# Bank_3.net
KiCad netlist of a schematic drawn in Altium Designer
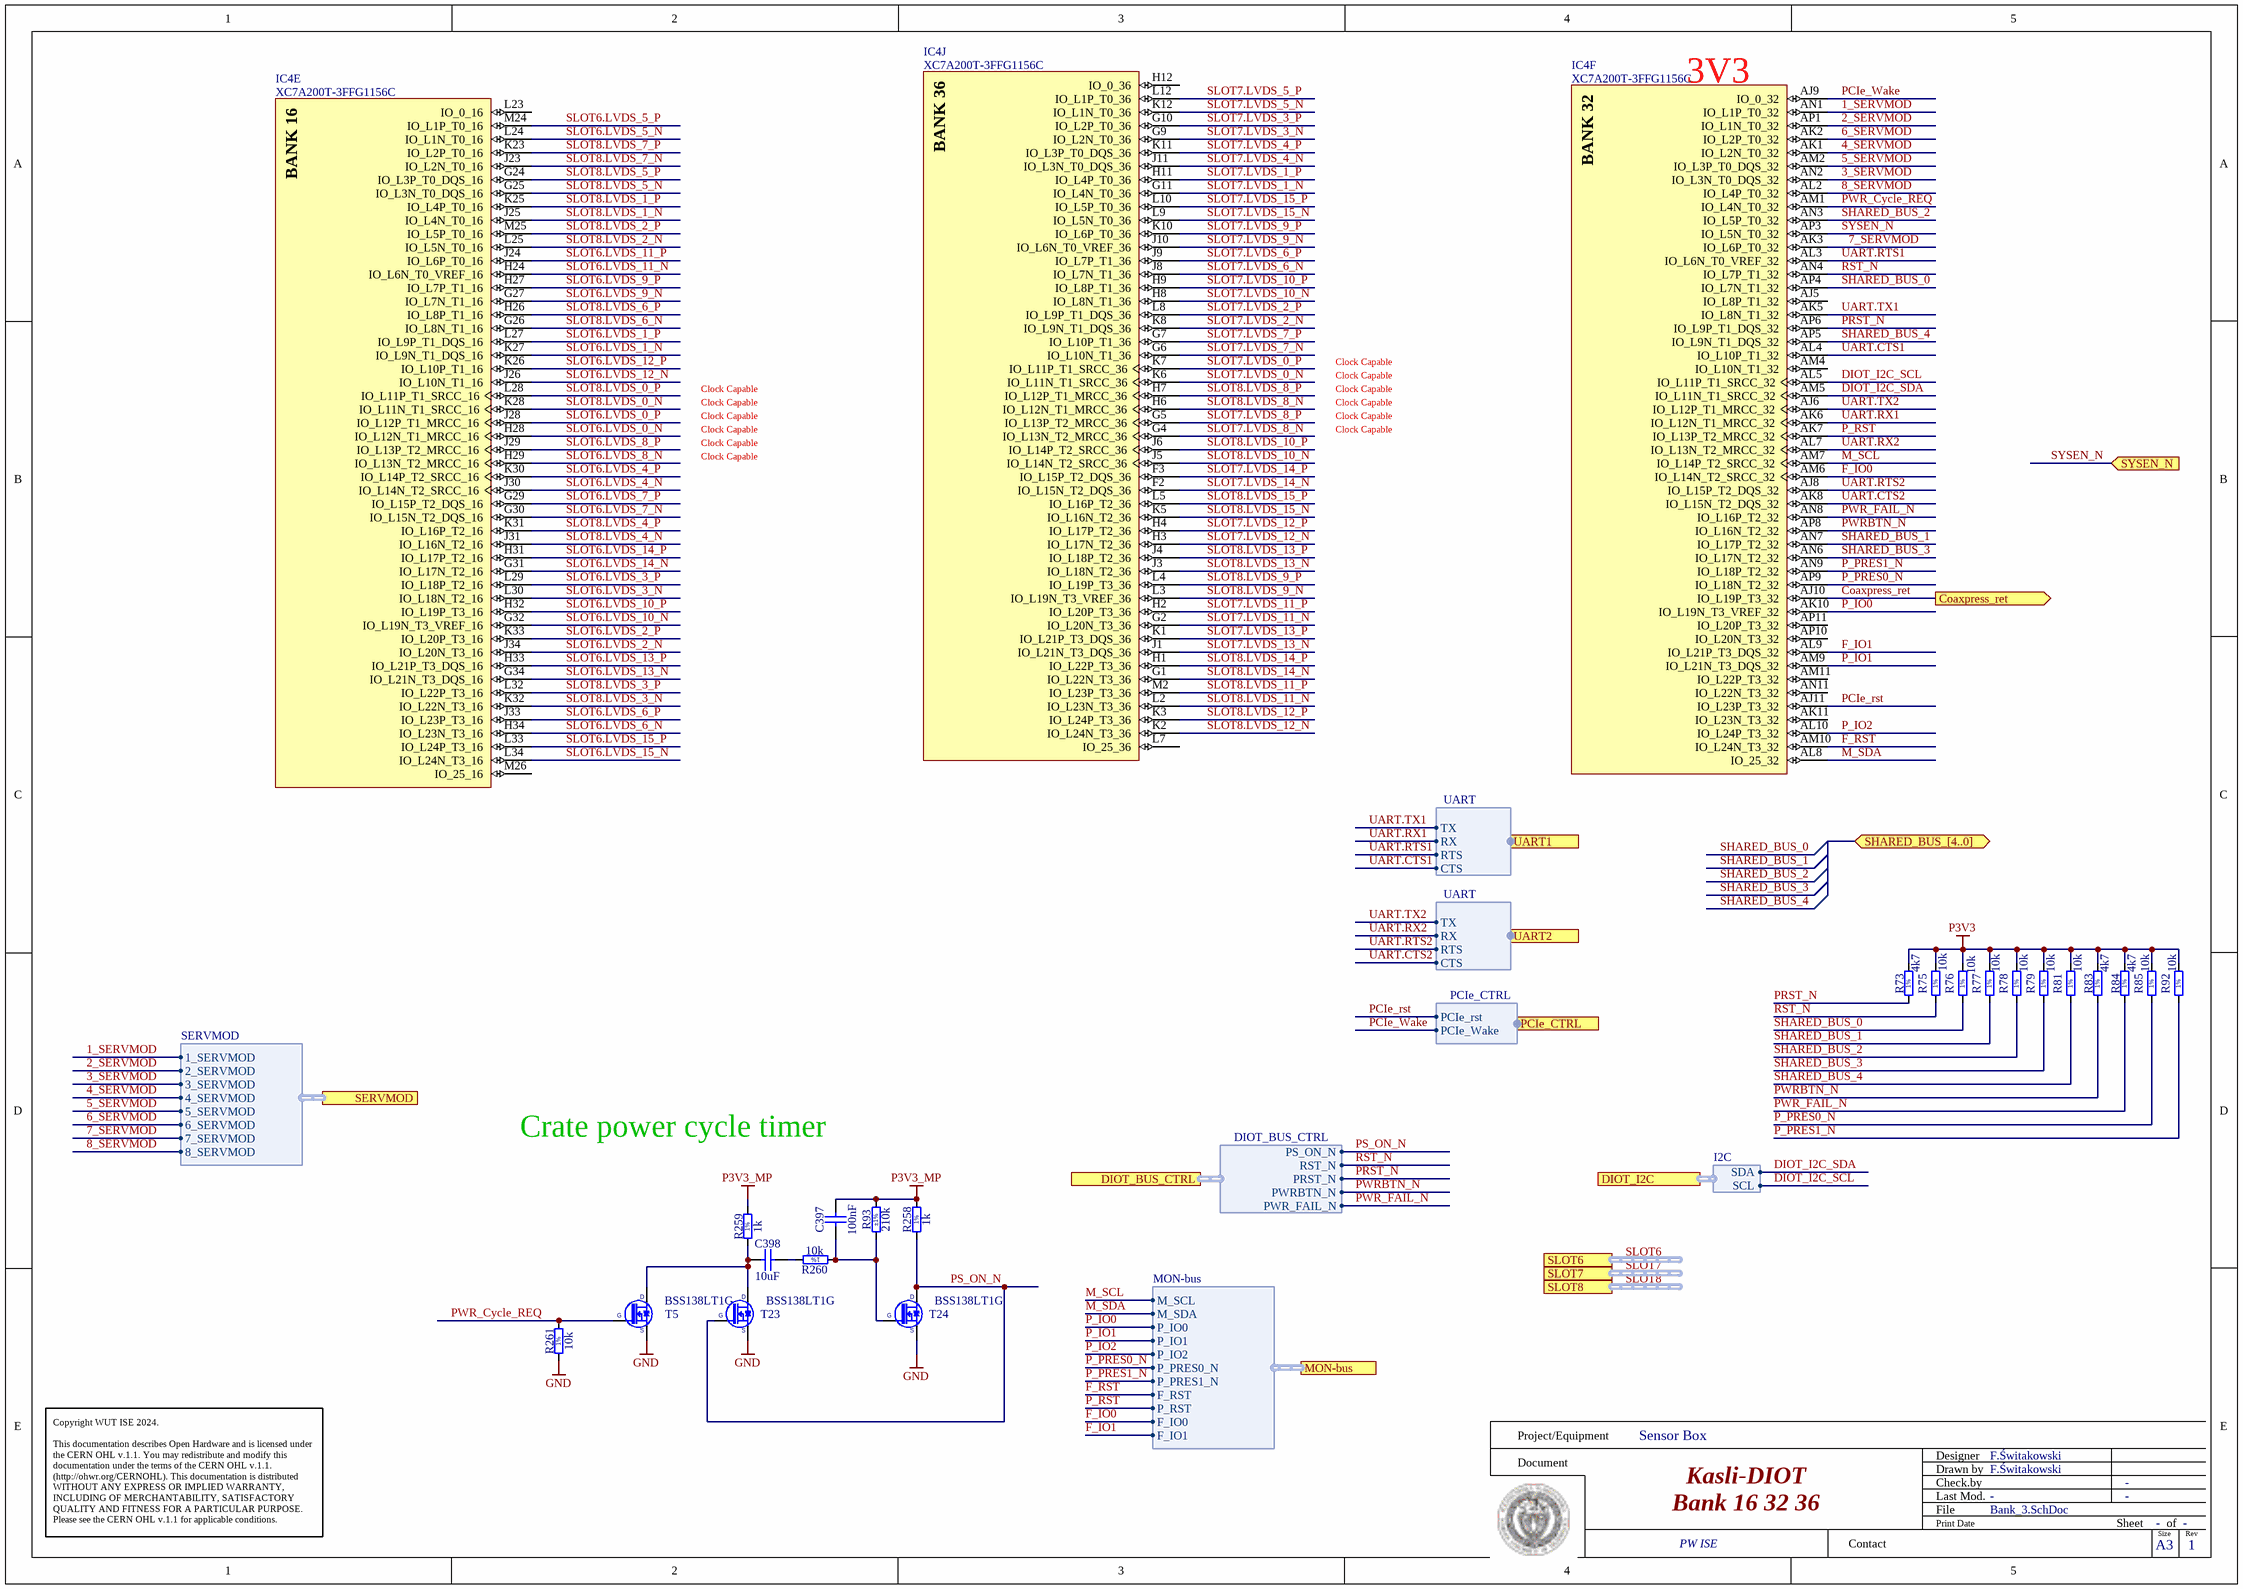
[diagram p0: Bank_3.SchDoc]

(export (version "E")
  (design (tool "Eeschema 10.0.6"))
  (components
    (comp (ref "C397")
      (value "100nF")
      (footprint "CAPC1005X55N")
      (description "Non-polarised capacitor")
      (fields
        (field (name "PART NUMBER") "CC0402_100NF_16V_10%_X7R")
        (field (name "VOLTAGE") "16V")
        (field (name "AUTHOR") "CERN DEM JLC")
      )
      (libsource (lib "Capacitors") (part "Capacitor - non polarized"))
    )
    (comp (ref "C398")
      (value "10uF")
      (footprint "CAPC3216X180N")
      (description "Non-polarised capacitor")
      (fields
        (field (name "PART NUMBER") "CC1206_10UF_25V_10%_X7R")
        (field (name "VOLTAGE") "25V")
        (field (name "AUTHOR") "CERN DEM JLC")
      )
      (libsource (lib "Capacitors") (part "Capacitor - non polarized"))
    )
    (comp (ref "IC4")
      (value "XC7A200T-3FFG1156C")
      (footprint "BGA1156C100P34X34_3500X3500X310")
      (description "Artix-7 FPGA, 500 User I/Os, 16 GTP, 1156-Ball BGA, , Speed Grade 3, Commercial Grade, Pb-Free")
      (fields (field (name "MANUFACTURER") "XILINX") (field (name "AUTHOR") "CERN DEM JLC"))
      (libsource (lib "ICs And Semiconductors") (part "XC7A200T-3FFG1156C"))
    )
    (comp (ref "R73")
      (value "4k7")
      (footprint "RESC1005X40N")
      (description "Resistor - 1%")
      (fields
        (field (name "PART NUMBER") "R0402_4K7_1%_0.0625W_100PPM")
        (field (name "POWER") "0.0625W")
        (field (name "AUTHOR") "CERN DEM JLC")
      )
      (libsource (lib "Resistors") (part "Resistor - 1%"))
    )
    (comp (ref "R75")
      (value "10k")
      (footprint "RESC1005X40N")
      (description "Resistor - 1%")
      (fields
        (field (name "PART NUMBER") "R0402_10K_1%_0.0625W_100PPM")
        (field (name "POWER") "0.0625W")
        (field (name "AUTHOR") "CERN DEM JLC")
      )
      (libsource (lib "Resistors") (part "Resistor - 1%"))
    )
    (comp (ref "R76")
      (value "10k")
      (footprint "RESC1005X40N")
      (description "Resistor - 1%")
      (fields
        (field (name "PART NUMBER") "R0402_10K_1%_0.0625W_100PPM")
        (field (name "POWER") "0.0625W")
        (field (name "AUTHOR") "CERN DEM JLC")
      )
      (libsource (lib "Resistors") (part "Resistor - 1%"))
    )
    (comp (ref "R77")
      (value "10k")
      (footprint "RESC1005X40N")
      (description "Resistor - 1%")
      (fields
        (field (name "PART NUMBER") "R0402_10K_1%_0.0625W_100PPM")
        (field (name "POWER") "0.0625W")
        (field (name "AUTHOR") "CERN DEM JLC")
      )
      (libsource (lib "Resistors") (part "Resistor - 1%"))
    )
    (comp (ref "R78")
      (value "10k")
      (footprint "RESC1005X40N")
      (description "Resistor - 1%")
      (fields
        (field (name "PART NUMBER") "R0402_10K_1%_0.0625W_100PPM")
        (field (name "POWER") "0.0625W")
        (field (name "AUTHOR") "CERN DEM JLC")
      )
      (libsource (lib "Resistors") (part "Resistor - 1%"))
    )
    (comp (ref "R79")
      (value "10k")
      (footprint "RESC1005X40N")
      (description "Resistor - 1%")
      (fields
        (field (name "PART NUMBER") "R0402_10K_1%_0.0625W_100PPM")
        (field (name "POWER") "0.0625W")
        (field (name "AUTHOR") "CERN DEM JLC")
      )
      (libsource (lib "Resistors") (part "Resistor - 1%"))
    )
    (comp (ref "R81")
      (value "10k")
      (footprint "RESC1005X40N")
      (description "Resistor - 1%")
      (fields
        (field (name "PART NUMBER") "R0402_10K_1%_0.0625W_100PPM")
        (field (name "POWER") "0.0625W")
        (field (name "AUTHOR") "CERN DEM JLC")
      )
      (libsource (lib "Resistors") (part "Resistor - 1%"))
    )
    (comp (ref "R83")
      (value "4k7")
      (footprint "RESC1005X40N")
      (description "Resistor - 1%")
      (fields
        (field (name "PART NUMBER") "R0402_4K7_1%_0.0625W_100PPM")
        (field (name "POWER") "0.0625W")
        (field (name "AUTHOR") "CERN DEM JLC")
      )
      (libsource (lib "Resistors") (part "Resistor - 1%"))
    )
    (comp (ref "R84")
      (value "4k7")
      (footprint "RESC1005X40N")
      (description "Resistor - 1%")
      (fields
        (field (name "PART NUMBER") "R0402_4K7_1%_0.0625W_100PPM")
        (field (name "POWER") "0.0625W")
        (field (name "AUTHOR") "CERN DEM JLC")
      )
      (libsource (lib "Resistors") (part "Resistor - 1%"))
    )
    (comp (ref "R85")
      (value "10k")
      (footprint "RESC1005X40N")
      (description "Resistor - 1%")
      (fields
        (field (name "PART NUMBER") "R0402_10K_1%_0.0625W_100PPM")
        (field (name "POWER") "0.0625W")
        (field (name "AUTHOR") "CERN DEM JLC")
      )
      (libsource (lib "Resistors") (part "Resistor - 1%"))
    )
    (comp (ref "R92")
      (value "10k")
      (footprint "RESC1005X40N")
      (description "Resistor - 1%")
      (fields
        (field (name "PART NUMBER") "R0402_10K_1%_0.0625W_100PPM")
        (field (name "POWER") "0.0625W")
        (field (name "AUTHOR") "CERN DEM JLC")
      )
      (libsource (lib "Resistors") (part "Resistor - 1%"))
    )
    (comp (ref "R93")
      (value "210k")
      (footprint "RESC1005X40N")
      (description "Resistor - 1%")
      (fields
        (field (name "TOLERANCE") "±1%")
        (field (name "PART NUMBER") "R0402_210K_1%_0.063W_100PPM")
        (field (name "POWER") "0.063W")
        (field (name "AUTHOR") "CERN DEM BC")
      )
      (libsource (lib "Resistors") (part "Resistor - 1%"))
    )
    (comp (ref "R258")
      (value "1k")
      (footprint "RESC1005X40N")
      (description "Resistor - 1%")
      (fields
        (field (name "PART NUMBER") "R0402_1K_1%_0.0625W_100PPM")
        (field (name "POWER") "0.0625W")
        (field (name "AUTHOR") "CERN DEM JLC")
      )
      (libsource (lib "Resistors") (part "Resistor - 1%"))
    )
    (comp (ref "R259")
      (value "1k")
      (footprint "RESC1005X40N")
      (description "Resistor - 1%")
      (fields
        (field (name "PART NUMBER") "R0402_1K_1%_0.0625W_100PPM")
        (field (name "POWER") "0.0625W")
        (field (name "AUTHOR") "CERN DEM JLC")
      )
      (libsource (lib "Resistors") (part "Resistor - 1%"))
    )
    (comp (ref "R260")
      (value "10k")
      (footprint "RESC1005X40N")
      (description "Resistor - 1%")
      (fields
        (field (name "PART NUMBER") "R0402_10K_1%_0.0625W_100PPM")
        (field (name "POWER") "0.0625W")
        (field (name "AUTHOR") "CERN DEM JLC")
      )
      (libsource (lib "Resistors") (part "Resistor - 1%"))
    )
    (comp (ref "R261")
      (value "10k")
      (footprint "RESC1005X40N")
      (description "Resistor - 1%")
      (fields
        (field (name "PART NUMBER") "R0402_10K_1%_0.0625W_100PPM")
        (field (name "POWER") "0.0625W")
        (field (name "AUTHOR") "CERN DEM JLC")
      )
      (libsource (lib "Resistors") (part "Resistor - 1%"))
    )
    (comp (ref "T5")
      (value "BSS138LT1G")
      (footprint "SOT95P240X110-3N")
      (description "N-CHANNEL MOSFET WITH DIODE")
      (fields
        (field (name "MANUFACTURER") "ON SEMICONDUCTOR")
        (field (name "MANUFACTURER PART NUMBER") "BSS138L")
        (field (name "AUTHOR") "CERN DEM JLC")
      )
      (libsource (lib "ICs And Semiconductors") (part "N-MOSFET-D 1G 2S 3D"))
    )
    (comp (ref "T23")
      (value "BSS138LT1G")
      (footprint "SOT95P240X110-3N")
      (description "N-CHANNEL MOSFET WITH DIODE")
      (fields
        (field (name "MANUFACTURER") "ON SEMICONDUCTOR")
        (field (name "MANUFACTURER PART NUMBER") "BSS138L")
        (field (name "AUTHOR") "CERN DEM JLC")
      )
      (libsource (lib "ICs And Semiconductors") (part "N-MOSFET-D 1G 2S 3D"))
    )
    (comp (ref "T24")
      (value "BSS138LT1G")
      (footprint "SOT95P240X110-3N")
      (description "N-CHANNEL MOSFET WITH DIODE")
      (fields
        (field (name "MANUFACTURER") "ON SEMICONDUCTOR")
        (field (name "MANUFACTURER PART NUMBER") "BSS138L")
        (field (name "AUTHOR") "CERN DEM JLC")
      )
      (libsource (lib "ICs And Semiconductors") (part "N-MOSFET-D 1G 2S 3D"))
    )
  )
  (nets
    (net (code "10") (name "/1_SERVMOD") (class "Default")
      (node (ref "IC4") (pin "AN1") (pinfunction "IO_L1P_T0_32_AN1") (pintype "bidirectional"))
    )
    (net (code "11") (name "/2_SERVMOD") (class "Default")
      (node (ref "IC4") (pin "AP1") (pinfunction "IO_L1N_T0_32_AP1") (pintype "bidirectional"))
    )
    (net (code "12") (name "/3_SERVMOD") (class "Default")
      (node (ref "IC4") (pin "AN2") (pinfunction "IO_L3N_T0_DQS_32_AN2") (pintype "bidirectional"))
    )
    (net (code "13") (name "/4_SERVMOD") (class "Default")
      (node (ref "IC4") (pin "AK1") (pinfunction "IO_L2N_T0_32_AK1") (pintype "bidirectional"))
    )
    (net (code "14") (name "/5_SERVMOD") (class "Default")
      (node (ref "IC4") (pin "AM2") (pinfunction "IO_L3P_T0_DQS_32_AM2") (pintype "bidirectional"))
    )
    (net (code "15") (name "/6_SERVMOD") (class "Default")
      (node (ref "IC4") (pin "AK2") (pinfunction "IO_L2P_T0_32_AK2") (pintype "bidirectional"))
    )
    (net (code "16") (name "/7_SERVMOD") (class "Default")
      (node (ref "IC4") (pin "AK3") (pinfunction "IO_L6P_T0_32_AK3") (pintype "bidirectional"))
    )
    (net (code "17") (name "/8_SERVMOD") (class "Default")
      (node (ref "IC4") (pin "AL2") (pinfunction "IO_L4P_T0_32_AL2") (pintype "bidirectional"))
    )
    (net (code "18") (name "/Coaxpress_ret") (class "Default")
      (node (ref "IC4") (pin "AJ10") (pinfunction "IO_L19P_T3_32_AJ10") (pintype "bidirectional"))
    )
    (net (code "19") (name "/DIOT_I2C_SCL") (class "Default")
      (node (ref "IC4") (pin "AL5") (pinfunction "IO_L11P_T1_SRCC_32_AL5") (pintype "bidirectional"))
    )
    (net (code "20") (name "/DIOT_I2C_SDA") (class "Default")
      (node (ref "IC4") (pin "AM5") (pinfunction "IO_L11N_T1_SRCC_32_AM5") (pintype "bidirectional"))
    )
    (net (code "21") (name "/F_IO0") (class "Default")
      (node (ref "IC4") (pin "AM6") (pinfunction "IO_L14N_T2_SRCC_32_AM6") (pintype "bidirectional"))
    )
    (net (code "22") (name "/F_IO1") (class "Default")
      (node (ref "IC4") (pin "AL9") (pinfunction "IO_L21P_T3_DQS_32_AL9") (pintype "bidirectional"))
    )
    (net (code "23") (name "/F_RST") (class "Default")
      (node (ref "IC4") (pin "AM10") (pinfunction "IO_L24N_T3_32_AM10") (pintype "bidirectional"))
    )
    (net (code "24") (name "/M_SCL") (class "Default")
      (node (ref "IC4") (pin "AM7") (pinfunction "IO_L14P_T2_SRCC_32_AM7") (pintype "bidirectional"))
    )
    (net (code "25") (name "/M_SDA") (class "Default")
      (node (ref "IC4") (pin "AL8") (pinfunction "IO_25_32_AL8") (pintype "bidirectional"))
    )
    (net (code "26") (name "/PCIe_Wake") (class "Default")
      (node (ref "IC4") (pin "AJ9") (pinfunction "IO_0_32_AJ9") (pintype "bidirectional"))
    )
    (net (code "27") (name "/PCIe_rst") (class "Default")
      (node (ref "IC4") (pin "AJ11") (pinfunction "IO_L23P_T3_32_AJ11") (pintype "bidirectional"))
    )
    (net (code "28") (name "/PRST_N") (class "Default")
      (node (ref "IC4") (pin "AP6") (pinfunction "IO_L9P_T1_DQS_32_AP6") (pintype "bidirectional"))
      (node (ref "R73") (pin "1") (pinfunction "1_1") (pintype "passive"))
    )
    (net (code "29") (name "/PS_ON_N") (class "Default")
      (node (ref "R258") (pin "1") (pinfunction "1_1") (pintype "passive"))
      (node (ref "T23") (pin "1") (pinfunction "G_1") (pintype "passive"))
      (node (ref "T24") (pin "3") (pinfunction "D_3") (pintype "passive"))
    )
    (net (code "30") (name "/PWRBTN_N") (class "Default")
      (node (ref "IC4") (pin "AP8") (pinfunction "IO_L16N_T2_32_AP8") (pintype "bidirectional"))
      (node (ref "R83") (pin "1") (pinfunction "1_1") (pintype "passive"))
    )
    (net (code "31") (name "/PWR_Cycle_REQ") (class "Default")
      (node (ref "IC4") (pin "AM1") (pinfunction "IO_L4N_T0_32_AM1") (pintype "bidirectional"))
      (node (ref "R261") (pin "2") (pinfunction "2_2") (pintype "passive"))
      (node (ref "T5") (pin "1") (pinfunction "G_1") (pintype "passive"))
    )
    (net (code "32") (name "/PWR_FAIL_N") (class "Default")
      (node (ref "IC4") (pin "AN8") (pinfunction "IO_L16P_T2_32_AN8") (pintype "bidirectional"))
      (node (ref "R84") (pin "1") (pinfunction "1_1") (pintype "passive"))
    )
    (net (code "33") (name "/P_IO0") (class "Default")
      (node (ref "IC4") (pin "AK10") (pinfunction "IO_L19N_T3_VREF_32_AK10") (pintype "bidirectional"))
    )
    (net (code "34") (name "/P_IO1") (class "Default")
      (node (ref "IC4") (pin "AM9") (pinfunction "IO_L21N_T3_DQS_32_AM9") (pintype "bidirectional"))
    )
    (net (code "35") (name "/P_IO2") (class "Default")
      (node (ref "IC4") (pin "AL10") (pinfunction "IO_L24P_T3_32_AL10") (pintype "bidirectional"))
    )
    (net (code "36") (name "/P_PRES0_N") (class "Default")
      (node (ref "IC4") (pin "AP9") (pinfunction "IO_L18N_T2_32_AP9") (pintype "bidirectional"))
      (node (ref "R85") (pin "1") (pinfunction "1_1") (pintype "passive"))
    )
    (net (code "37") (name "/P_PRES1_N") (class "Default")
      (node (ref "IC4") (pin "AN9") (pinfunction "IO_L18P_T2_32_AN9") (pintype "bidirectional"))
      (node (ref "R92") (pin "1") (pinfunction "1_1") (pintype "passive"))
    )
    (net (code "38") (name "/P_RST") (class "Default")
      (node (ref "IC4") (pin "AK7") (pinfunction "IO_L13P_T2_MRCC_32_AK7") (pintype "bidirectional"))
    )
    (net (code "39") (name "/RST_N") (class "Default")
      (node (ref "IC4") (pin "AN4") (pinfunction "IO_L7P_T1_32_AN4") (pintype "bidirectional"))
      (node (ref "R75") (pin "1") (pinfunction "1_1") (pintype "passive"))
    )
    (net (code "40") (name "/SHARED_BUS_0") (class "Default")
      (node (ref "IC4") (pin "AP4") (pinfunction "IO_L7N_T1_32_AP4") (pintype "bidirectional"))
      (node (ref "R76") (pin "1") (pinfunction "1_1") (pintype "passive"))
    )
    (net (code "41") (name "/SHARED_BUS_1") (class "Default")
      (node (ref "IC4") (pin "AN7") (pinfunction "IO_L17P_T2_32_AN7") (pintype "bidirectional"))
      (node (ref "R77") (pin "1") (pinfunction "1_1") (pintype "passive"))
    )
    (net (code "42") (name "/SHARED_BUS_2") (class "Default")
      (node (ref "IC4") (pin "AN3") (pinfunction "IO_L5P_T0_32_AN3") (pintype "bidirectional"))
      (node (ref "R78") (pin "1") (pinfunction "1_1") (pintype "passive"))
    )
    (net (code "43") (name "/SHARED_BUS_3") (class "Default")
      (node (ref "IC4") (pin "AN6") (pinfunction "IO_L17N_T2_32_AN6") (pintype "bidirectional"))
      (node (ref "R79") (pin "1") (pinfunction "1_1") (pintype "passive"))
    )
    (net (code "44") (name "/SHARED_BUS_4") (class "Default")
      (node (ref "IC4") (pin "AP5") (pinfunction "IO_L9N_T1_DQS_32_AP5") (pintype "bidirectional"))
      (node (ref "R81") (pin "1") (pinfunction "1_1") (pintype "passive"))
    )
    (net (code "46") (name "/SLOT6.LVDS_0_N") (class "Default")
      (node (ref "IC4") (pin "H28") (pinfunction "IO_L12N_T1_MRCC_16_H28") (pintype "bidirectional"))
    )
    (net (code "47") (name "/SLOT6.LVDS_0_P") (class "Default")
      (node (ref "IC4") (pin "J28") (pinfunction "IO_L12P_T1_MRCC_16_J28") (pintype "bidirectional"))
    )
    (net (code "48") (name "/SLOT6.LVDS_1_N") (class "Default")
      (node (ref "IC4") (pin "K27") (pinfunction "IO_L9N_T1_DQS_16_K27") (pintype "bidirectional"))
    )
    (net (code "49") (name "/SLOT6.LVDS_1_P") (class "Default")
      (node (ref "IC4") (pin "L27") (pinfunction "IO_L9P_T1_DQS_16_L27") (pintype "bidirectional"))
    )
    (net (code "50") (name "/SLOT6.LVDS_2_N") (class "Default")
      (node (ref "IC4") (pin "J34") (pinfunction "IO_L20N_T3_16_J34") (pintype "bidirectional"))
    )
    (net (code "51") (name "/SLOT6.LVDS_2_P") (class "Default")
      (node (ref "IC4") (pin "K33") (pinfunction "IO_L20P_T3_16_K33") (pintype "bidirectional"))
    )
    (net (code "52") (name "/SLOT6.LVDS_3_N") (class "Default")
      (node (ref "IC4") (pin "L30") (pinfunction "IO_L18N_T2_16_L30") (pintype "bidirectional"))
    )
    (net (code "53") (name "/SLOT6.LVDS_3_P") (class "Default")
      (node (ref "IC4") (pin "L29") (pinfunction "IO_L18P_T2_16_L29") (pintype "bidirectional"))
    )
    (net (code "54") (name "/SLOT6.LVDS_4_N") (class "Default")
      (node (ref "IC4") (pin "J30") (pinfunction "IO_L14N_T2_SRCC_16_J30") (pintype "bidirectional"))
    )
    (net (code "55") (name "/SLOT6.LVDS_4_P") (class "Default")
      (node (ref "IC4") (pin "K30") (pinfunction "IO_L14P_T2_SRCC_16_K30") (pintype "bidirectional"))
    )
    (net (code "56") (name "/SLOT6.LVDS_5_N") (class "Default")
      (node (ref "IC4") (pin "L24") (pinfunction "IO_L1N_T0_16_L24") (pintype "bidirectional"))
    )
    (net (code "57") (name "/SLOT6.LVDS_5_P") (class "Default")
      (node (ref "IC4") (pin "M24") (pinfunction "IO_L1P_T0_16_M24") (pintype "bidirectional"))
    )
    (net (code "58") (name "/SLOT6.LVDS_6_N") (class "Default")
      (node (ref "IC4") (pin "H34") (pinfunction "IO_L23N_T3_16_H34") (pintype "bidirectional"))
    )
    (net (code "59") (name "/SLOT6.LVDS_6_P") (class "Default")
      (node (ref "IC4") (pin "J33") (pinfunction "IO_L23P_T3_16_J33") (pintype "bidirectional"))
    )
    (net (code "60") (name "/SLOT6.LVDS_7_N") (class "Default")
      (node (ref "IC4") (pin "G30") (pinfunction "IO_L15N_T2_DQS_16_G30") (pintype "bidirectional"))
    )
    (net (code "61") (name "/SLOT6.LVDS_7_P") (class "Default")
      (node (ref "IC4") (pin "G29") (pinfunction "IO_L15P_T2_DQS_16_G29") (pintype "bidirectional"))
    )
    (net (code "62") (name "/SLOT6.LVDS_8_N") (class "Default")
      (node (ref "IC4") (pin "H29") (pinfunction "IO_L13N_T2_MRCC_16_H29") (pintype "bidirectional"))
    )
    (net (code "63") (name "/SLOT6.LVDS_8_P") (class "Default")
      (node (ref "IC4") (pin "J29") (pinfunction "IO_L13P_T2_MRCC_16_J29") (pintype "bidirectional"))
    )
    (net (code "64") (name "/SLOT6.LVDS_9_N") (class "Default")
      (node (ref "IC4") (pin "G27") (pinfunction "IO_L7N_T1_16_G27") (pintype "bidirectional"))
    )
    (net (code "65") (name "/SLOT6.LVDS_9_P") (class "Default")
      (node (ref "IC4") (pin "H27") (pinfunction "IO_L7P_T1_16_H27") (pintype "bidirectional"))
    )
    (net (code "66") (name "/SLOT6.LVDS_10_N") (class "Default")
      (node (ref "IC4") (pin "G32") (pinfunction "IO_L19N_T3_VREF_16_G32") (pintype "bidirectional"))
    )
    (net (code "67") (name "/SLOT6.LVDS_10_P") (class "Default")
      (node (ref "IC4") (pin "H32") (pinfunction "IO_L19P_T3_16_H32") (pintype "bidirectional"))
    )
    (net (code "68") (name "/SLOT6.LVDS_11_N") (class "Default")
      (node (ref "IC4") (pin "H24") (pinfunction "IO_L6N_T0_VREF_16_H24") (pintype "bidirectional"))
    )
    (net (code "69") (name "/SLOT6.LVDS_11_P") (class "Default")
      (node (ref "IC4") (pin "J24") (pinfunction "IO_L6P_T0_16_J24") (pintype "bidirectional"))
    )
    (net (code "70") (name "/SLOT6.LVDS_12_N") (class "Default")
      (node (ref "IC4") (pin "J26") (pinfunction "IO_L10N_T1_16_J26") (pintype "bidirectional"))
    )
    (net (code "71") (name "/SLOT6.LVDS_12_P") (class "Default")
      (node (ref "IC4") (pin "K26") (pinfunction "IO_L10P_T1_16_K26") (pintype "bidirectional"))
    )
    (net (code "72") (name "/SLOT6.LVDS_13_N") (class "Default")
      (node (ref "IC4") (pin "G34") (pinfunction "IO_L21N_T3_DQS_16_G34") (pintype "bidirectional"))
    )
    (net (code "73") (name "/SLOT6.LVDS_13_P") (class "Default")
      (node (ref "IC4") (pin "H33") (pinfunction "IO_L21P_T3_DQS_16_H33") (pintype "bidirectional"))
    )
    (net (code "74") (name "/SLOT6.LVDS_14_N") (class "Default")
      (node (ref "IC4") (pin "G31") (pinfunction "IO_L17N_T2_16_G31") (pintype "bidirectional"))
    )
    (net (code "75") (name "/SLOT6.LVDS_14_P") (class "Default")
      (node (ref "IC4") (pin "H31") (pinfunction "IO_L17P_T2_16_H31") (pintype "bidirectional"))
    )
    (net (code "76") (name "/SLOT6.LVDS_15_N") (class "Default")
      (node (ref "IC4") (pin "L34") (pinfunction "IO_L24N_T3_16_L34") (pintype "bidirectional"))
    )
    (net (code "77") (name "/SLOT6.LVDS_15_P") (class "Default")
      (node (ref "IC4") (pin "L33") (pinfunction "IO_L24P_T3_16_L33") (pintype "bidirectional"))
    )
    (net (code "78") (name "/SLOT7.LVDS_0_N") (class "Default")
      (node (ref "IC4") (pin "K6") (pinfunction "IO_L11N_T1_SRCC_36_K6") (pintype "bidirectional"))
    )
    (net (code "79") (name "/SLOT7.LVDS_0_P") (class "Default")
      (node (ref "IC4") (pin "K7") (pinfunction "IO_L11P_T1_SRCC_36_K7") (pintype "bidirectional"))
    )
    (net (code "80") (name "/SLOT7.LVDS_1_N") (class "Default")
      (node (ref "IC4") (pin "G11") (pinfunction "IO_L4N_T0_36_G11") (pintype "bidirectional"))
    )
    (net (code "81") (name "/SLOT7.LVDS_1_P") (class "Default")
      (node (ref "IC4") (pin "H11") (pinfunction "IO_L4P_T0_36_H11") (pintype "bidirectional"))
    )
    (net (code "82") (name "/SLOT7.LVDS_2_N") (class "Default")
      (node (ref "IC4") (pin "K8") (pinfunction "IO_L9N_T1_DQS_36_K8") (pintype "bidirectional"))
    )
    (net (code "83") (name "/SLOT7.LVDS_2_P") (class "Default")
      (node (ref "IC4") (pin "L8") (pinfunction "IO_L9P_T1_DQS_36_L8") (pintype "bidirectional"))
    )
    (net (code "84") (name "/SLOT7.LVDS_3_N") (class "Default")
      (node (ref "IC4") (pin "G9") (pinfunction "IO_L2N_T0_36_G9") (pintype "bidirectional"))
    )
    (net (code "85") (name "/SLOT7.LVDS_3_P") (class "Default")
      (node (ref "IC4") (pin "G10") (pinfunction "IO_L2P_T0_36_G10") (pintype "bidirectional"))
    )
    (net (code "86") (name "/SLOT7.LVDS_4_N") (class "Default")
      (node (ref "IC4") (pin "J11") (pinfunction "IO_L3N_T0_DQS_36_J11") (pintype "bidirectional"))
    )
    (net (code "87") (name "/SLOT7.LVDS_4_P") (class "Default")
      (node (ref "IC4") (pin "K11") (pinfunction "IO_L3P_T0_DQS_36_K11") (pintype "bidirectional"))
    )
    (net (code "88") (name "/SLOT7.LVDS_5_N") (class "Default")
      (node (ref "IC4") (pin "K12") (pinfunction "IO_L1N_T0_36_K12") (pintype "bidirectional"))
    )
    (net (code "89") (name "/SLOT7.LVDS_5_P") (class "Default")
      (node (ref "IC4") (pin "L12") (pinfunction "IO_L1P_T0_36_L12") (pintype "bidirectional"))
    )
    (net (code "90") (name "/SLOT7.LVDS_6_N") (class "Default")
      (node (ref "IC4") (pin "J8") (pinfunction "IO_L7N_T1_36_J8") (pintype "bidirectional"))
    )
    (net (code "91") (name "/SLOT7.LVDS_6_P") (class "Default")
      (node (ref "IC4") (pin "J9") (pinfunction "IO_L7P_T1_36_J9") (pintype "bidirectional"))
    )
    (net (code "92") (name "/SLOT7.LVDS_7_N") (class "Default")
      (node (ref "IC4") (pin "G6") (pinfunction "IO_L10N_T1_36_G6") (pintype "bidirectional"))
    )
    (net (code "93") (name "/SLOT7.LVDS_7_P") (class "Default")
      (node (ref "IC4") (pin "G7") (pinfunction "IO_L10P_T1_36_G7") (pintype "bidirectional"))
    )
    (net (code "94") (name "/SLOT7.LVDS_8_N") (class "Default")
      (node (ref "IC4") (pin "G4") (pinfunction "IO_L13N_T2_MRCC_36_G4") (pintype "bidirectional"))
    )
    (net (code "95") (name "/SLOT7.LVDS_8_P") (class "Default")
      (node (ref "IC4") (pin "G5") (pinfunction "IO_L13P_T2_MRCC_36_G5") (pintype "bidirectional"))
    )
    (net (code "96") (name "/SLOT7.LVDS_9_N") (class "Default")
      (node (ref "IC4") (pin "J10") (pinfunction "IO_L6N_T0_VREF_36_J10") (pintype "bidirectional"))
    )
    (net (code "97") (name "/SLOT7.LVDS_9_P") (class "Default")
      (node (ref "IC4") (pin "K10") (pinfunction "IO_L6P_T0_36_K10") (pintype "bidirectional"))
    )
    (net (code "98") (name "/SLOT7.LVDS_10_N") (class "Default")
      (node (ref "IC4") (pin "H8") (pinfunction "IO_L8N_T1_36_H8") (pintype "bidirectional"))
    )
    (net (code "99") (name "/SLOT7.LVDS_10_P") (class "Default")
      (node (ref "IC4") (pin "H9") (pinfunction "IO_L8P_T1_36_H9") (pintype "bidirectional"))
    )
    (net (code "100") (name "/SLOT7.LVDS_11_N") (class "Default")
      (node (ref "IC4") (pin "G2") (pinfunction "IO_L20N_T3_36_G2") (pintype "bidirectional"))
    )
    (net (code "101") (name "/SLOT7.LVDS_11_P") (class "Default")
      (node (ref "IC4") (pin "H2") (pinfunction "IO_L20P_T3_36_H2") (pintype "bidirectional"))
    )
    (net (code "102") (name "/SLOT7.LVDS_12_N") (class "Default")
      (node (ref "IC4") (pin "H3") (pinfunction "IO_L17N_T2_36_H3") (pintype "bidirectional"))
    )
    (net (code "103") (name "/SLOT7.LVDS_12_P") (class "Default")
      (node (ref "IC4") (pin "H4") (pinfunction "IO_L17P_T2_36_H4") (pintype "bidirectional"))
    )
    (net (code "104") (name "/SLOT7.LVDS_13_N") (class "Default")
      (node (ref "IC4") (pin "J1") (pinfunction "IO_L21N_T3_DQS_36_J1") (pintype "bidirectional"))
    )
    (net (code "105") (name "/SLOT7.LVDS_13_P") (class "Default")
      (node (ref "IC4") (pin "K1") (pinfunction "IO_L21P_T3_DQS_36_K1") (pintype "bidirectional"))
    )
    (net (code "106") (name "/SLOT7.LVDS_14_N") (class "Default")
      (node (ref "IC4") (pin "F2") (pinfunction "IO_L15N_T2_DQS_36_F2") (pintype "bidirectional"))
    )
    (net (code "107") (name "/SLOT7.LVDS_14_P") (class "Default")
      (node (ref "IC4") (pin "F3") (pinfunction "IO_L15P_T2_DQS_36_F3") (pintype "bidirectional"))
    )
    (net (code "108") (name "/SLOT7.LVDS_15_N") (class "Default")
      (node (ref "IC4") (pin "L9") (pinfunction "IO_L5N_T0_36_L9") (pintype "bidirectional"))
    )
    (net (code "109") (name "/SLOT7.LVDS_15_P") (class "Default")
      (node (ref "IC4") (pin "L10") (pinfunction "IO_L5P_T0_36_L10") (pintype "bidirectional"))
    )
    (net (code "110") (name "/SLOT8.LVDS_0_N") (class "Default")
      (node (ref "IC4") (pin "K28") (pinfunction "IO_L11N_T1_SRCC_16_K28") (pintype "bidirectional"))
    )
    (net (code "111") (name "/SLOT8.LVDS_0_P") (class "Default")
      (node (ref "IC4") (pin "L28") (pinfunction "IO_L11P_T1_SRCC_16_L28") (pintype "bidirectional"))
    )
    (net (code "112") (name "/SLOT8.LVDS_1_N") (class "Default")
      (node (ref "IC4") (pin "J25") (pinfunction "IO_L4N_T0_16_J25") (pintype "bidirectional"))
    )
    (net (code "113") (name "/SLOT8.LVDS_1_P") (class "Default")
      (node (ref "IC4") (pin "K25") (pinfunction "IO_L4P_T0_16_K25") (pintype "bidirectional"))
    )
    (net (code "114") (name "/SLOT8.LVDS_2_N") (class "Default")
      (node (ref "IC4") (pin "L25") (pinfunction "IO_L5N_T0_16_L25") (pintype "bidirectional"))
    )
    (net (code "115") (name "/SLOT8.LVDS_2_P") (class "Default")
      (node (ref "IC4") (pin "M25") (pinfunction "IO_L5P_T0_16_M25") (pintype "bidirectional"))
    )
    (net (code "116") (name "/SLOT8.LVDS_3_N") (class "Default")
      (node (ref "IC4") (pin "K32") (pinfunction "IO_L22N_T3_16_K32") (pintype "bidirectional"))
    )
    (net (code "117") (name "/SLOT8.LVDS_3_P") (class "Default")
      (node (ref "IC4") (pin "L32") (pinfunction "IO_L22P_T3_16_L32") (pintype "bidirectional"))
    )
    (net (code "118") (name "/SLOT8.LVDS_4_N") (class "Default")
      (node (ref "IC4") (pin "J31") (pinfunction "IO_L16N_T2_16_J31") (pintype "bidirectional"))
    )
    (net (code "119") (name "/SLOT8.LVDS_4_P") (class "Default")
      (node (ref "IC4") (pin "K31") (pinfunction "IO_L16P_T2_16_K31") (pintype "bidirectional"))
    )
    (net (code "120") (name "/SLOT8.LVDS_5_N") (class "Default")
      (node (ref "IC4") (pin "G25") (pinfunction "IO_L3N_T0_DQS_16_G25") (pintype "bidirectional"))
    )
    (net (code "121") (name "/SLOT8.LVDS_5_P") (class "Default")
      (node (ref "IC4") (pin "G24") (pinfunction "IO_L3P_T0_DQS_16_G24") (pintype "bidirectional"))
    )
    (net (code "122") (name "/SLOT8.LVDS_6_N") (class "Default")
      (node (ref "IC4") (pin "G26") (pinfunction "IO_L8N_T1_16_G26") (pintype "bidirectional"))
    )
    (net (code "123") (name "/SLOT8.LVDS_6_P") (class "Default")
      (node (ref "IC4") (pin "H26") (pinfunction "IO_L8P_T1_16_H26") (pintype "bidirectional"))
    )
    (net (code "124") (name "/SLOT8.LVDS_7_N") (class "Default")
      (node (ref "IC4") (pin "J23") (pinfunction "IO_L2N_T0_16_J23") (pintype "bidirectional"))
    )
    (net (code "125") (name "/SLOT8.LVDS_7_P") (class "Default")
      (node (ref "IC4") (pin "K23") (pinfunction "IO_L2P_T0_16_K23") (pintype "bidirectional"))
    )
    (net (code "126") (name "/SLOT8.LVDS_8_N") (class "Default")
      (node (ref "IC4") (pin "H6") (pinfunction "IO_L12N_T1_MRCC_36_H6") (pintype "bidirectional"))
    )
    (net (code "127") (name "/SLOT8.LVDS_8_P") (class "Default")
      (node (ref "IC4") (pin "H7") (pinfunction "IO_L12P_T1_MRCC_36_H7") (pintype "bidirectional"))
    )
    (net (code "128") (name "/SLOT8.LVDS_9_N") (class "Default")
      (node (ref "IC4") (pin "L3") (pinfunction "IO_L19N_T3_VREF_36_L3") (pintype "bidirectional"))
    )
    (net (code "129") (name "/SLOT8.LVDS_9_P") (class "Default")
      (node (ref "IC4") (pin "L4") (pinfunction "IO_L19P_T3_36_L4") (pintype "bidirectional"))
    )
    (net (code "130") (name "/SLOT8.LVDS_10_N") (class "Default")
      (node (ref "IC4") (pin "J5") (pinfunction "IO_L14N_T2_SRCC_36_J5") (pintype "bidirectional"))
    )
    (net (code "131") (name "/SLOT8.LVDS_10_P") (class "Default")
      (node (ref "IC4") (pin "J6") (pinfunction "IO_L14P_T2_SRCC_36_J6") (pintype "bidirectional"))
    )
    (net (code "132") (name "/SLOT8.LVDS_11_N") (class "Default")
      (node (ref "IC4") (pin "L2") (pinfunction "IO_L23N_T3_36_L2") (pintype "bidirectional"))
    )
    (net (code "133") (name "/SLOT8.LVDS_11_P") (class "Default")
      (node (ref "IC4") (pin "M2") (pinfunction "IO_L23P_T3_36_M2") (pintype "bidirectional"))
    )
    (net (code "134") (name "/SLOT8.LVDS_12_N") (class "Default")
      (node (ref "IC4") (pin "K2") (pinfunction "IO_L24N_T3_36_K2") (pintype "bidirectional"))
    )
    (net (code "135") (name "/SLOT8.LVDS_12_P") (class "Default")
      (node (ref "IC4") (pin "K3") (pinfunction "IO_L24P_T3_36_K3") (pintype "bidirectional"))
    )
    (net (code "136") (name "/SLOT8.LVDS_13_N") (class "Default")
      (node (ref "IC4") (pin "J3") (pinfunction "IO_L18N_T2_36_J3") (pintype "bidirectional"))
    )
    (net (code "137") (name "/SLOT8.LVDS_13_P") (class "Default")
      (node (ref "IC4") (pin "J4") (pinfunction "IO_L18P_T2_36_J4") (pintype "bidirectional"))
    )
    (net (code "138") (name "/SLOT8.LVDS_14_N") (class "Default")
      (node (ref "IC4") (pin "G1") (pinfunction "IO_L22N_T3_36_G1") (pintype "bidirectional"))
    )
    (net (code "139") (name "/SLOT8.LVDS_14_P") (class "Default")
      (node (ref "IC4") (pin "H1") (pinfunction "IO_L22P_T3_36_H1") (pintype "bidirectional"))
    )
    (net (code "140") (name "/SLOT8.LVDS_15_N") (class "Default")
      (node (ref "IC4") (pin "K5") (pinfunction "IO_L16N_T2_36_K5") (pintype "bidirectional"))
    )
    (net (code "141") (name "/SLOT8.LVDS_15_P") (class "Default")
      (node (ref "IC4") (pin "L5") (pinfunction "IO_L16P_T2_36_L5") (pintype "bidirectional"))
    )
    (net (code "142") (name "/SYSEN_N") (class "Default")
      (node (ref "IC4") (pin "AP3") (pinfunction "IO_L5N_T0_32_AP3") (pintype "bidirectional"))
    )
    (net (code "143") (name "/UART.CTS1") (class "Default")
      (node (ref "IC4") (pin "AL4") (pinfunction "IO_L10P_T1_32_AL4") (pintype "bidirectional"))
    )
    (net (code "144") (name "/UART.CTS2") (class "Default")
      (node (ref "IC4") (pin "AK8") (pinfunction "IO_L15N_T2_DQS_32_AK8") (pintype "bidirectional"))
    )
    (net (code "145") (name "/UART.RTS1") (class "Default")
      (node (ref "IC4") (pin "AL3") (pinfunction "IO_L6N_T0_VREF_32_AL3") (pintype "bidirectional"))
    )
    (net (code "146") (name "/UART.RTS2") (class "Default")
      (node (ref "IC4") (pin "AJ8") (pinfunction "IO_L15P_T2_DQS_32_AJ8") (pintype "bidirectional"))
    )
    (net (code "147") (name "/UART.RX1") (class "Default")
      (node (ref "IC4") (pin "AK6") (pinfunction "IO_L12N_T1_MRCC_32_AK6") (pintype "bidirectional"))
    )
    (net (code "148") (name "/UART.RX2") (class "Default")
      (node (ref "IC4") (pin "AL7") (pinfunction "IO_L13N_T2_MRCC_32_AL7") (pintype "bidirectional"))
    )
    (net (code "149") (name "/UART.TX1") (class "Default")
      (node (ref "IC4") (pin "AK5") (pinfunction "IO_L8N_T1_32_AK5") (pintype "bidirectional"))
    )
    (net (code "150") (name "/UART.TX2") (class "Default")
      (node (ref "IC4") (pin "AJ6") (pinfunction "IO_L12P_T1_MRCC_32_AJ6") (pintype "bidirectional"))
    )
    (net (code "160") (name "GND") (class "Default")
      (node (ref "R261") (pin "1") (pinfunction "1_1") (pintype "passive"))
      (node (ref "T23") (pin "2") (pinfunction "S_2") (pintype "passive"))
      (node (ref "T24") (pin "2") (pinfunction "S_2") (pintype "passive"))
      (node (ref "T5") (pin "2") (pinfunction "S_2") (pintype "passive"))
    )
    (net (code "161") (name "Net-(C398-Pad2)") (class "Default")
      (node (ref "C398") (pin "2") (pinfunction "2_2") (pintype "passive"))
      (node (ref "R260") (pin "2") (pinfunction "2_2") (pintype "passive"))
    )
    (net (code "162") (name "Net-(T23-D)") (class "Default")
      (node (ref "C398") (pin "1") (pinfunction "1_1") (pintype "passive"))
      (node (ref "R259") (pin "1") (pinfunction "1_1") (pintype "passive"))
      (node (ref "T23") (pin "3") (pinfunction "D_3") (pintype "passive"))
      (node (ref "T5") (pin "3") (pinfunction "D_3") (pintype "passive"))
    )
    (net (code "163") (name "Net-(T24-G)") (class "Default")
      (node (ref "C397") (pin "1") (pinfunction "1_1") (pintype "passive"))
      (node (ref "R260") (pin "1") (pinfunction "1_1") (pintype "passive"))
      (node (ref "R93") (pin "1") (pinfunction "1_1") (pintype "passive"))
      (node (ref "T24") (pin "1") (pinfunction "G_1") (pintype "passive"))
    )
    (net (code "164") (name "P3V3") (class "Default")
      (node (ref "R73") (pin "2") (pinfunction "2_2") (pintype "passive"))
      (node (ref "R75") (pin "2") (pinfunction "2_2") (pintype "passive"))
      (node (ref "R76") (pin "2") (pinfunction "2_2") (pintype "passive"))
      (node (ref "R77") (pin "2") (pinfunction "2_2") (pintype "passive"))
      (node (ref "R78") (pin "2") (pinfunction "2_2") (pintype "passive"))
      (node (ref "R79") (pin "2") (pinfunction "2_2") (pintype "passive"))
      (node (ref "R81") (pin "2") (pinfunction "2_2") (pintype "passive"))
      (node (ref "R83") (pin "2") (pinfunction "2_2") (pintype "passive"))
      (node (ref "R84") (pin "2") (pinfunction "2_2") (pintype "passive"))
      (node (ref "R85") (pin "2") (pinfunction "2_2") (pintype "passive"))
      (node (ref "R92") (pin "2") (pinfunction "2_2") (pintype "passive"))
    )
    (net (code "165") (name "P3V3_MP") (class "Default")
      (node (ref "C397") (pin "2") (pinfunction "2_2") (pintype "passive"))
      (node (ref "R258") (pin "2") (pinfunction "2_2") (pintype "passive"))
      (node (ref "R259") (pin "2") (pinfunction "2_2") (pintype "passive"))
      (node (ref "R93") (pin "2") (pinfunction "2_2") (pintype "passive"))
    )
    (net (code "166") (name "unconnected-(IC4E-IO_0_16-PadL23)") (class "Default")
      (node (ref "IC4") (pin "L23") (pinfunction "IO_0_16_L23") (pintype "bidirectional"))
    )
    (net (code "167") (name "unconnected-(IC4E-IO_25_16-PadM26)") (class "Default")
      (node (ref "IC4") (pin "M26") (pinfunction "IO_25_16_M26") (pintype "bidirectional"))
    )
    (net (code "168") (name "unconnected-(IC4F-IO_L8P_T1_32-PadAJ5)") (class "Default")
      (node (ref "IC4") (pin "AJ5") (pinfunction "IO_L8P_T1_32_AJ5") (pintype "bidirectional"))
    )
    (net (code "169") (name "unconnected-(IC4F-IO_L10N_T1_32-PadAM4)") (class "Default")
      (node (ref "IC4") (pin "AM4") (pinfunction "IO_L10N_T1_32_AM4") (pintype "bidirectional"))
    )
    (net (code "170") (name "unconnected-(IC4F-IO_L20N_T3_32-PadAP10)") (class "Default")
      (node (ref "IC4") (pin "AP10") (pinfunction "IO_L20N_T3_32_AP10") (pintype "bidirectional"))
    )
    (net (code "171") (name "unconnected-(IC4F-IO_L20P_T3_32-PadAP11)") (class "Default")
      (node (ref "IC4") (pin "AP11") (pinfunction "IO_L20P_T3_32_AP11") (pintype "bidirectional"))
    )
    (net (code "172") (name "unconnected-(IC4F-IO_L22N_T3_32-PadAN11)") (class "Default")
      (node (ref "IC4") (pin "AN11") (pinfunction "IO_L22N_T3_32_AN11") (pintype "bidirectional"))
    )
    (net (code "173") (name "unconnected-(IC4F-IO_L22P_T3_32-PadAM11)") (class "Default")
      (node (ref "IC4") (pin "AM11") (pinfunction "IO_L22P_T3_32_AM11") (pintype "bidirectional"))
    )
    (net (code "174") (name "unconnected-(IC4F-IO_L23N_T3_32-PadAK11)") (class "Default")
      (node (ref "IC4") (pin "AK11") (pinfunction "IO_L23N_T3_32_AK11") (pintype "bidirectional"))
    )
    (net (code "175") (name "unconnected-(IC4J-IO_0_36-PadH12)") (class "Default")
      (node (ref "IC4") (pin "H12") (pinfunction "IO_0_36_H12") (pintype "bidirectional"))
    )
    (net (code "176") (name "unconnected-(IC4J-IO_25_36-PadL7)") (class "Default")
      (node (ref "IC4") (pin "L7") (pinfunction "IO_25_36_L7") (pintype "bidirectional"))
    )
  )
)
